# PWR.net
KiCad netlist of a schematic drawn in Altium Designer
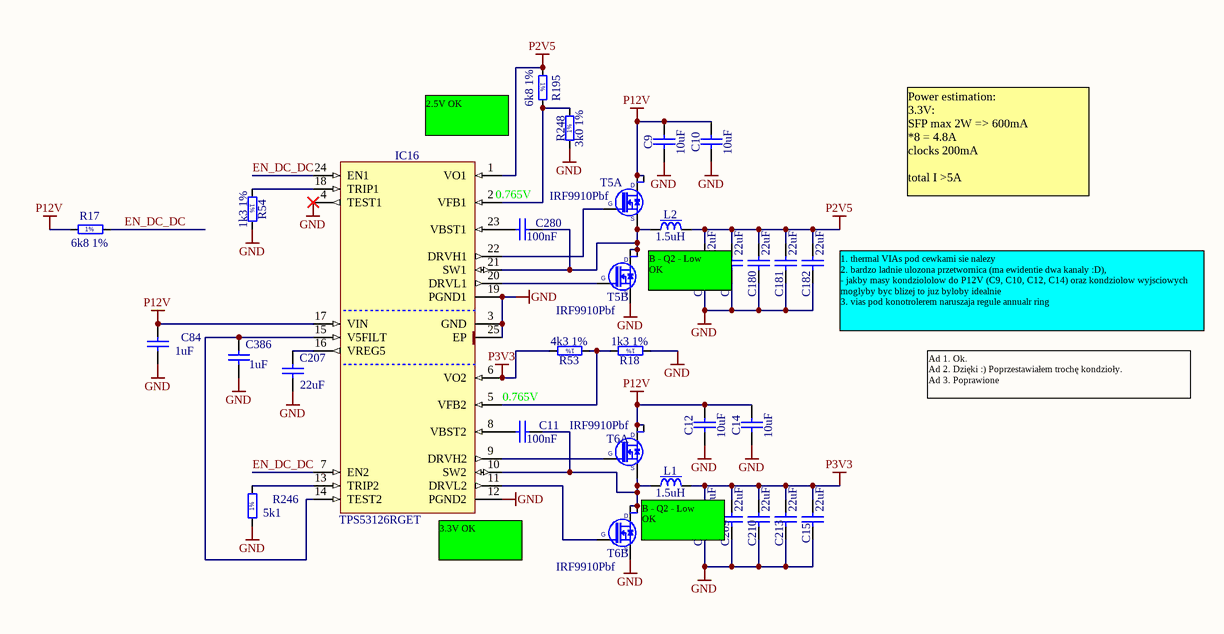
[diagram p0: PWR.SchDoc]

(export (version "E")
  (design (tool "Eeschema 10.0.6"))
  (components
    (comp (ref "C9")
      (value "10uF")
      (footprint "CAPC3216X140N")
      (description "Non-polarised capacitor")
      (fields
        (field (name "PART NUMBER") "CC1206_10UF_16V_10%_X7R")
        (field (name "VOLTAGE") "16V")
        (field (name "AUTHOR") "CERN DEM JLC")
      )
      (libsource (lib "Capacitors") (part "Capacitor - non polarized"))
    )
    (comp (ref "C10")
      (value "10uF")
      (footprint "CAPC3216X140N")
      (description "Non-polarised capacitor")
      (fields
        (field (name "PART NUMBER") "CC1206_10UF_16V_10%_X7R")
        (field (name "VOLTAGE") "16V")
        (field (name "AUTHOR") "CERN DEM JLC")
      )
      (libsource (lib "Capacitors") (part "Capacitor - non polarized"))
    )
    (comp (ref "C11")
      (value "100nF")
      (footprint "CAPC1608X87N")
      (description "Non-polarised capacitor")
      (fields
        (field (name "PART NUMBER") "CC0603_100NF_50V_10%_X7R")
        (field (name "VOLTAGE") "50V")
        (field (name "AUTHOR") "CERN DEM JLC")
      )
      (libsource (lib "Capacitors") (part "Capacitor - non polarized"))
    )
    (comp (ref "C12")
      (value "10uF")
      (footprint "CAPC3216X140N")
      (description "Non-polarised capacitor")
      (fields
        (field (name "PART NUMBER") "CC1206_10UF_16V_10%_X7R")
        (field (name "VOLTAGE") "16V")
        (field (name "AUTHOR") "CERN DEM JLC")
      )
      (libsource (lib "Capacitors") (part "Capacitor - non polarized"))
    )
    (comp (ref "C14")
      (value "10uF")
      (footprint "CAPC3216X140N")
      (description "Non-polarised capacitor")
      (fields
        (field (name "PART NUMBER") "CC1206_10UF_16V_10%_X7R")
        (field (name "VOLTAGE") "16V")
        (field (name "AUTHOR") "CERN DEM JLC")
      )
      (libsource (lib "Capacitors") (part "Capacitor - non polarized"))
    )
    (comp (ref "C15")
      (value "22uF")
      (footprint "CAPC3216X180N")
      (description "Non-polarised capacitor")
      (fields
        (field (name "PART NUMBER") "CC1206_22UF_10V_10%_X7R")
        (field (name "VOLTAGE") "10V")
        (field (name "AUTHOR") "CERN DEM JLC")
      )
      (libsource (lib "Capacitors") (part "Capacitor - non polarized"))
    )
    (comp (ref "C84")
      (value "1uF")
      (footprint "CAPC1608X87N")
      (description "Non-polarised capacitor")
      (fields
        (field (name "PART NUMBER") "CC0603_1UF_16V_10%_X7R")
        (field (name "VOLTAGE") "16V")
        (field (name "AUTHOR") "CERN DEM JLC")
      )
      (libsource (lib "Capacitors") (part "Capacitor - non polarized"))
    )
    (comp (ref "C176")
      (value "22uF")
      (footprint "CAPC3216X180N")
      (description "Non-polarised capacitor")
      (fields
        (field (name "PART NUMBER") "CC1206_22UF_10V_10%_X7R")
        (field (name "VOLTAGE") "10V")
        (field (name "AUTHOR") "CERN DEM JLC")
      )
      (libsource (lib "Capacitors") (part "Capacitor - non polarized"))
    )
    (comp (ref "C179")
      (value "22uF")
      (footprint "CAPC3216X180N")
      (description "Non-polarised capacitor")
      (fields
        (field (name "PART NUMBER") "CC1206_22UF_10V_10%_X7R")
        (field (name "VOLTAGE") "10V")
        (field (name "AUTHOR") "CERN DEM JLC")
      )
      (libsource (lib "Capacitors") (part "Capacitor - non polarized"))
    )
    (comp (ref "C180")
      (value "22uF")
      (footprint "CAPC3216X180N")
      (description "Non-polarised capacitor")
      (fields
        (field (name "PART NUMBER") "CC1206_22UF_10V_10%_X7R")
        (field (name "VOLTAGE") "10V")
        (field (name "AUTHOR") "CERN DEM JLC")
      )
      (libsource (lib "Capacitors") (part "Capacitor - non polarized"))
    )
    (comp (ref "C181")
      (value "22uF")
      (footprint "CAPC3216X180N")
      (description "Non-polarised capacitor")
      (fields
        (field (name "PART NUMBER") "CC1206_22UF_10V_10%_X7R")
        (field (name "VOLTAGE") "10V")
        (field (name "AUTHOR") "CERN DEM JLC")
      )
      (libsource (lib "Capacitors") (part "Capacitor - non polarized"))
    )
    (comp (ref "C182")
      (value "22uF")
      (footprint "CAPC3216X180N")
      (description "Non-polarised capacitor")
      (fields
        (field (name "PART NUMBER") "CC1206_22UF_10V_10%_X7R")
        (field (name "VOLTAGE") "10V")
        (field (name "AUTHOR") "CERN DEM JLC")
      )
      (libsource (lib "Capacitors") (part "Capacitor - non polarized"))
    )
    (comp (ref "C207")
      (value "22uF")
      (footprint "CAPC3216X180N")
      (description "Non-polarised capacitor")
      (fields
        (field (name "PART NUMBER") "CC1206_22UF_10V_10%_X7R")
        (field (name "VOLTAGE") "10V")
        (field (name "AUTHOR") "CERN DEM JLC")
      )
      (libsource (lib "Capacitors") (part "Capacitor - non polarized"))
    )
    (comp (ref "C208")
      (value "22uF")
      (footprint "CAPC3216X180N")
      (description "Non-polarised capacitor")
      (fields
        (field (name "PART NUMBER") "CC1206_22UF_10V_10%_X7R")
        (field (name "VOLTAGE") "10V")
        (field (name "AUTHOR") "CERN DEM JLC")
      )
      (libsource (lib "Capacitors") (part "Capacitor - non polarized"))
    )
    (comp (ref "C209")
      (value "22uF")
      (footprint "CAPC3216X180N")
      (description "Non-polarised capacitor")
      (fields
        (field (name "PART NUMBER") "CC1206_22UF_10V_10%_X7R")
        (field (name "VOLTAGE") "10V")
        (field (name "AUTHOR") "CERN DEM JLC")
      )
      (libsource (lib "Capacitors") (part "Capacitor - non polarized"))
    )
    (comp (ref "C210")
      (value "22uF")
      (footprint "CAPC3216X180N")
      (description "Non-polarised capacitor")
      (fields
        (field (name "PART NUMBER") "CC1206_22UF_10V_10%_X7R")
        (field (name "VOLTAGE") "10V")
        (field (name "AUTHOR") "CERN DEM JLC")
      )
      (libsource (lib "Capacitors") (part "Capacitor - non polarized"))
    )
    (comp (ref "C213")
      (value "22uF")
      (footprint "CAPC3216X180N")
      (description "Non-polarised capacitor")
      (fields
        (field (name "PART NUMBER") "CC1206_22UF_10V_10%_X7R")
        (field (name "VOLTAGE") "10V")
        (field (name "AUTHOR") "CERN DEM JLC")
      )
      (libsource (lib "Capacitors") (part "Capacitor - non polarized"))
    )
    (comp (ref "C280")
      (value "100nF")
      (footprint "CAPC1608X87N")
      (description "Non-polarised capacitor")
      (fields
        (field (name "PART NUMBER") "CC0603_100NF_50V_10%_X7R")
        (field (name "VOLTAGE") "50V")
        (field (name "AUTHOR") "CERN DEM JLC")
      )
      (libsource (lib "Capacitors") (part "Capacitor - non polarized"))
    )
    (comp (ref "C386")
      (value "1uF")
      (footprint "CAPC1608X87N")
      (description "Non-polarised capacitor")
      (fields
        (field (name "PART NUMBER") "CC0603_1UF_16V_10%_X7R")
        (field (name "VOLTAGE") "16V")
        (field (name "AUTHOR") "CERN DEM JLC")
      )
      (libsource (lib "Capacitors") (part "Capacitor - non polarized"))
    )
    (comp (ref "IC16")
      (value "TPS53126RGET")
      (footprint "QFN50P400X400X100-25N-S255")
      (description "Dual Synchronous Step-Down Controller For Low Voltage Power Rails")
      (fields (field (name "MANUFACTURER") "TEXAS INSTRUMENTS") (field (name "AUTHOR") "CERN DEM JLC"))
      (libsource (lib "ICs And Semiconductors") (part "TPS53126RGET"))
    )
    (comp (ref "L1")
      (value "1.5uH")
      (footprint "INDM6965X300N")
      (description "Inductor With Magnetic core")
      (fields
        (field (name "PART NUMBER") "IND2525_1.5UH_20%_VISHAY_IHLP-2525CZ")
        (field (name "POWER") "9A")
        (field (name "AUTHOR") "CERN DEM JLC")
      )
      (libsource (lib "Inductors & Transformers") (part "Inductor With Magnetic core"))
    )
    (comp (ref "L2")
      (value "1.5uH")
      (footprint "INDM6965X300N")
      (description "Inductor With Magnetic core")
      (fields
        (field (name "PART NUMBER") "IND2525_1.5UH_20%_VISHAY_IHLP-2525CZ")
        (field (name "POWER") "9A")
        (field (name "AUTHOR") "CERN DEM JLC")
      )
      (libsource (lib "Inductors & Transformers") (part "Inductor With Magnetic core"))
    )
    (comp (ref "R17")
      (value "6k8 1%")
      (footprint "0603R")
      (description "Resistor - 1%")
      (fields
        (field (name "PART NUMBER") "R0603_6K8_1%_0.1W_100PPM")
        (field (name "POWER") "0.1W")
        (field (name "AUTHOR") "CERN DEM JLC")
      )
      (libsource (lib "Resistors") (part "Resistor - 1%"))
    )
    (comp (ref "R18")
      (value "1k3 1%")
      (footprint "0603R")
      (description "Resistor - 1%")
      (fields
        (field (name "PART NUMBER") "R0603_1K3_1%_0.1W_100PPM")
        (field (name "POWER") "0.1W")
        (field (name "AUTHOR") "CERN DEM JLC")
      )
      (libsource (lib "Resistors") (part "Resistor - 1%"))
    )
    (comp (ref "R53")
      (value "4k3 1%")
      (footprint "0603R")
      (description "Resistor - 1%")
      (fields
        (field (name "PART NUMBER") "R0603_4K3_1%_0.1W_100PPM")
        (field (name "POWER") "0.1W")
        (field (name "AUTHOR") "CERN DEM JLC")
      )
      (libsource (lib "Resistors") (part "Resistor - 1%"))
    )
    (comp (ref "R54")
      (value "1k3 1%")
      (footprint "0603R")
      (description "Resistor - 1%")
      (fields
        (field (name "PART NUMBER") "R0603_1K3_1%_0.1W_100PPM")
        (field (name "POWER") "0.1W")
        (field (name "AUTHOR") "CERN DEM JLC")
      )
      (libsource (lib "Resistors") (part "Resistor - 1%"))
    )
    (comp (ref "R195")
      (value "6k8 1%")
      (footprint "0603R")
      (description "Resistor - 1%")
      (fields
        (field (name "PART NUMBER") "R0603_6K8_1%_0.1W_100PPM")
        (field (name "POWER") "0.1W")
        (field (name "AUTHOR") "CERN DEM JLC")
      )
      (libsource (lib "Resistors") (part "Resistor - 1%"))
    )
    (comp (ref "R246")
      (value "5k1")
      (footprint "RESC1608X55N")
      (description "Resistor - 1%")
      (fields
        (field (name "PART NUMBER") "R0603_5K1_1%_0.1W_100PPM")
        (field (name "POWER") "0.1W")
        (field (name "AUTHOR") "CERN DEM JLC")
      )
      (libsource (lib "Resistors") (part "Resistor - 1%"))
    )
    (comp (ref "R248")
      (value "3k0 1%")
      (footprint "0603R")
      (description "Resistor - 1%")
      (fields
        (field (name "PART NUMBER") "R0603_3K_1%_0.1W_100PPM")
        (field (name "POWER") "0.1W")
        (field (name "AUTHOR") "CERN DEM JLC")
      )
      (libsource (lib "Resistors") (part "Resistor - 1%"))
    )
    (comp (ref "T5")
      (value "IRF9910Pbf")
      (footprint "SOIC127P600X175-8N")
      (description "Dual SO-8 MOSFET For POL Cconverter")
      (fields (field (name "MANUFACTURER") "INTERNATIONAL RECTIFIER") (field (name "AUTHOR") "CERN DEM JLC"))
      (libsource (lib "ICs And Semiconductors") (part "IRF9910"))
    )
    (comp (ref "T6")
      (value "IRF9910Pbf")
      (footprint "SOIC127P600X175-8N")
      (description "Dual SO-8 MOSFET For POL Cconverter")
      (fields (field (name "MANUFACTURER") "INTERNATIONAL RECTIFIER") (field (name "AUTHOR") "CERN DEM JLC"))
      (libsource (lib "ICs And Semiconductors") (part "IRF9910"))
    )
  )
  (nets
    (net (code "1") (name "/EN_DC_DC") (class "Default")
      (node (ref "IC16") (pin "24") (pinfunction "EN1_24") (pintype "input"))
      (node (ref "IC16") (pin "7") (pinfunction "EN2_7") (pintype "input"))
      (node (ref "R17") (pin "2") (pinfunction "2_2") (pintype "passive"))
    )
    (net (code "2") (name "GND") (class "Default")
      (node (ref "C10") (pin "1") (pinfunction "1_1") (pintype "passive"))
      (node (ref "C12") (pin "1") (pinfunction "1_1") (pintype "passive"))
      (node (ref "C14") (pin "1") (pinfunction "1_1") (pintype "passive"))
      (node (ref "C15") (pin "1") (pinfunction "1_1") (pintype "passive"))
      (node (ref "C176") (pin "1") (pinfunction "1_1") (pintype "passive"))
      (node (ref "C179") (pin "1") (pinfunction "1_1") (pintype "passive"))
      (node (ref "C180") (pin "1") (pinfunction "1_1") (pintype "passive"))
      (node (ref "C181") (pin "1") (pinfunction "1_1") (pintype "passive"))
      (node (ref "C182") (pin "1") (pinfunction "1_1") (pintype "passive"))
      (node (ref "C207") (pin "1") (pinfunction "1_1") (pintype "passive"))
      (node (ref "C208") (pin "1") (pinfunction "1_1") (pintype "passive"))
      (node (ref "C209") (pin "1") (pinfunction "1_1") (pintype "passive"))
      (node (ref "C210") (pin "1") (pinfunction "1_1") (pintype "passive"))
      (node (ref "C213") (pin "1") (pinfunction "1_1") (pintype "passive"))
      (node (ref "C386") (pin "1") (pinfunction "1_1") (pintype "passive"))
      (node (ref "C84") (pin "2") (pinfunction "2_2") (pintype "passive"))
      (node (ref "C9") (pin "1") (pinfunction "1_1") (pintype "passive"))
      (node (ref "IC16") (pin "12") (pinfunction "PGND2_12") (pintype "power_in"))
      (node (ref "IC16") (pin "19") (pinfunction "PGND1_19") (pintype "power_in"))
      (node (ref "IC16") (pin "25") (pinfunction "EP_25") (pintype "power_in"))
      (node (ref "IC16") (pin "3") (pinfunction "GND_3") (pintype "power_in"))
      (node (ref "IC16") (pin "4") (pinfunction "TEST1_4") (pintype "output"))
      (node (ref "R18") (pin "1") (pinfunction "1_1") (pintype "passive"))
      (node (ref "R246") (pin "1") (pinfunction "1_1") (pintype "passive"))
      (node (ref "R248") (pin "1") (pinfunction "1_1") (pintype "passive"))
      (node (ref "R54") (pin "2") (pinfunction "2_2") (pintype "passive"))
      (node (ref "T5") (pin "1") (pinfunction "S_1") (pintype "passive"))
      (node (ref "T6") (pin "1") (pinfunction "S_1") (pintype "passive"))
    )
    (net (code "3") (name "Net-(IC16-DRVH1)") (class "Default")
      (node (ref "IC16") (pin "22") (pinfunction "DRVH1_22") (pintype "output"))
      (node (ref "T5") (pin "4") (pinfunction "G_4") (pintype "passive"))
    )
    (net (code "4") (name "Net-(IC16-DRVH2)") (class "Default")
      (node (ref "IC16") (pin "9") (pinfunction "DRVH2_9") (pintype "output"))
      (node (ref "T6") (pin "4") (pinfunction "G_4") (pintype "passive"))
    )
    (net (code "5") (name "Net-(IC16-DRVL1)") (class "Default")
      (node (ref "IC16") (pin "20") (pinfunction "DRVL1_20") (pintype "output"))
      (node (ref "T5") (pin "2") (pinfunction "G_2") (pintype "passive"))
    )
    (net (code "6") (name "Net-(IC16-DRVL2)") (class "Default")
      (node (ref "IC16") (pin "11") (pinfunction "DRVL2_11") (pintype "output"))
      (node (ref "T6") (pin "2") (pinfunction "G_2") (pintype "passive"))
    )
    (net (code "7") (name "Net-(IC16-SW1)") (class "Default")
      (node (ref "C280") (pin "1") (pinfunction "1_1") (pintype "passive"))
      (node (ref "IC16") (pin "21") (pinfunction "SW1_21") (pintype "bidirectional"))
      (node (ref "L2") (pin "1") (pinfunction "1_1") (pintype "passive"))
      (node (ref "T5") (pin "3") (pinfunction "S_3") (pintype "passive"))
      (node (ref "T5") (pin "7") (pinfunction "D_7") (pintype "passive"))
      (node (ref "T5") (pin "8") (pinfunction "D_8") (pintype "passive"))
    )
    (net (code "8") (name "Net-(IC16-SW2)") (class "Default")
      (node (ref "C11") (pin "1") (pinfunction "1_1") (pintype "passive"))
      (node (ref "IC16") (pin "10") (pinfunction "SW2_10") (pintype "bidirectional"))
      (node (ref "L1") (pin "1") (pinfunction "1_1") (pintype "passive"))
      (node (ref "T6") (pin "3") (pinfunction "S_3") (pintype "passive"))
      (node (ref "T6") (pin "7") (pinfunction "D_7") (pintype "passive"))
      (node (ref "T6") (pin "8") (pinfunction "D_8") (pintype "passive"))
    )
    (net (code "9") (name "Net-(IC16-TEST2)") (class "Default")
      (node (ref "C386") (pin "2") (pinfunction "2_2") (pintype "passive"))
      (node (ref "IC16") (pin "14") (pinfunction "TEST2_14") (pintype "input"))
      (node (ref "IC16") (pin "15") (pinfunction "V5FILT_15") (pintype "input"))
    )
    (net (code "10") (name "Net-(IC16-TRIP1)") (class "Default")
      (node (ref "IC16") (pin "18") (pinfunction "TRIP1_18") (pintype "input"))
      (node (ref "R54") (pin "1") (pinfunction "1_1") (pintype "passive"))
    )
    (net (code "11") (name "Net-(IC16-TRIP2)") (class "Default")
      (node (ref "IC16") (pin "13") (pinfunction "TRIP2_13") (pintype "input"))
      (node (ref "R246") (pin "2") (pinfunction "2_2") (pintype "passive"))
    )
    (net (code "12") (name "Net-(IC16-VBST1)") (class "Default")
      (node (ref "C280") (pin "2") (pinfunction "2_2") (pintype "passive"))
      (node (ref "IC16") (pin "23") (pinfunction "VBST1_23") (pintype "input"))
    )
    (net (code "13") (name "Net-(IC16-VBST2)") (class "Default")
      (node (ref "C11") (pin "2") (pinfunction "2_2") (pintype "passive"))
      (node (ref "IC16") (pin "8") (pinfunction "VBST2_8") (pintype "input"))
    )
    (net (code "14") (name "Net-(IC16-VFB1)") (class "Default")
      (node (ref "IC16") (pin "2") (pinfunction "VFB1_2") (pintype "input"))
      (node (ref "R195") (pin "2") (pinfunction "2_2") (pintype "passive"))
      (node (ref "R248") (pin "2") (pinfunction "2_2") (pintype "passive"))
    )
    (net (code "15") (name "Net-(IC16-VFB2)") (class "Default")
      (node (ref "IC16") (pin "5") (pinfunction "VFB2_5") (pintype "input"))
      (node (ref "R18") (pin "2") (pinfunction "2_2") (pintype "passive"))
      (node (ref "R53") (pin "1") (pinfunction "1_1") (pintype "passive"))
    )
    (net (code "16") (name "Net-(IC16-VREG5)") (class "Default")
      (node (ref "C207") (pin "2") (pinfunction "2_2") (pintype "passive"))
      (node (ref "IC16") (pin "16") (pinfunction "VREG5_16") (pintype "output"))
    )
    (net (code "17") (name "P2V5") (class "Default")
      (node (ref "C176") (pin "2") (pinfunction "2_2") (pintype "passive"))
      (node (ref "C179") (pin "2") (pinfunction "2_2") (pintype "passive"))
      (node (ref "C180") (pin "2") (pinfunction "2_2") (pintype "passive"))
      (node (ref "C181") (pin "2") (pinfunction "2_2") (pintype "passive"))
      (node (ref "C182") (pin "2") (pinfunction "2_2") (pintype "passive"))
      (node (ref "IC16") (pin "1") (pinfunction "VO1_1") (pintype "input"))
      (node (ref "L2") (pin "2") (pinfunction "2_2") (pintype "passive"))
      (node (ref "R195") (pin "1") (pinfunction "1_1") (pintype "passive"))
    )
    (net (code "18") (name "P3V3") (class "Default")
      (node (ref "C15") (pin "2") (pinfunction "2_2") (pintype "passive"))
      (node (ref "C208") (pin "2") (pinfunction "2_2") (pintype "passive"))
      (node (ref "C209") (pin "2") (pinfunction "2_2") (pintype "passive"))
      (node (ref "C210") (pin "2") (pinfunction "2_2") (pintype "passive"))
      (node (ref "C213") (pin "2") (pinfunction "2_2") (pintype "passive"))
      (node (ref "IC16") (pin "6") (pinfunction "VO2_6") (pintype "input"))
      (node (ref "L1") (pin "2") (pinfunction "2_2") (pintype "passive"))
      (node (ref "R53") (pin "2") (pinfunction "2_2") (pintype "passive"))
    )
    (net (code "19") (name "P12V") (class "Default")
      (node (ref "C10") (pin "2") (pinfunction "2_2") (pintype "passive"))
      (node (ref "C12") (pin "2") (pinfunction "2_2") (pintype "passive"))
      (node (ref "C14") (pin "2") (pinfunction "2_2") (pintype "passive"))
      (node (ref "C84") (pin "1") (pinfunction "1_1") (pintype "passive"))
      (node (ref "C9") (pin "2") (pinfunction "2_2") (pintype "passive"))
      (node (ref "IC16") (pin "17") (pinfunction "VIN_17") (pintype "input"))
      (node (ref "R17") (pin "1") (pinfunction "1_1") (pintype "passive"))
      (node (ref "T5") (pin "5") (pinfunction "D_5") (pintype "passive"))
      (node (ref "T5") (pin "6") (pinfunction "D_6") (pintype "passive"))
      (node (ref "T6") (pin "5") (pinfunction "D_5") (pintype "passive"))
      (node (ref "T6") (pin "6") (pinfunction "D_6") (pintype "passive"))
    )
  )
)
